# Sheet1.net
KiCad netlist of a schematic drawn in Altium Designer
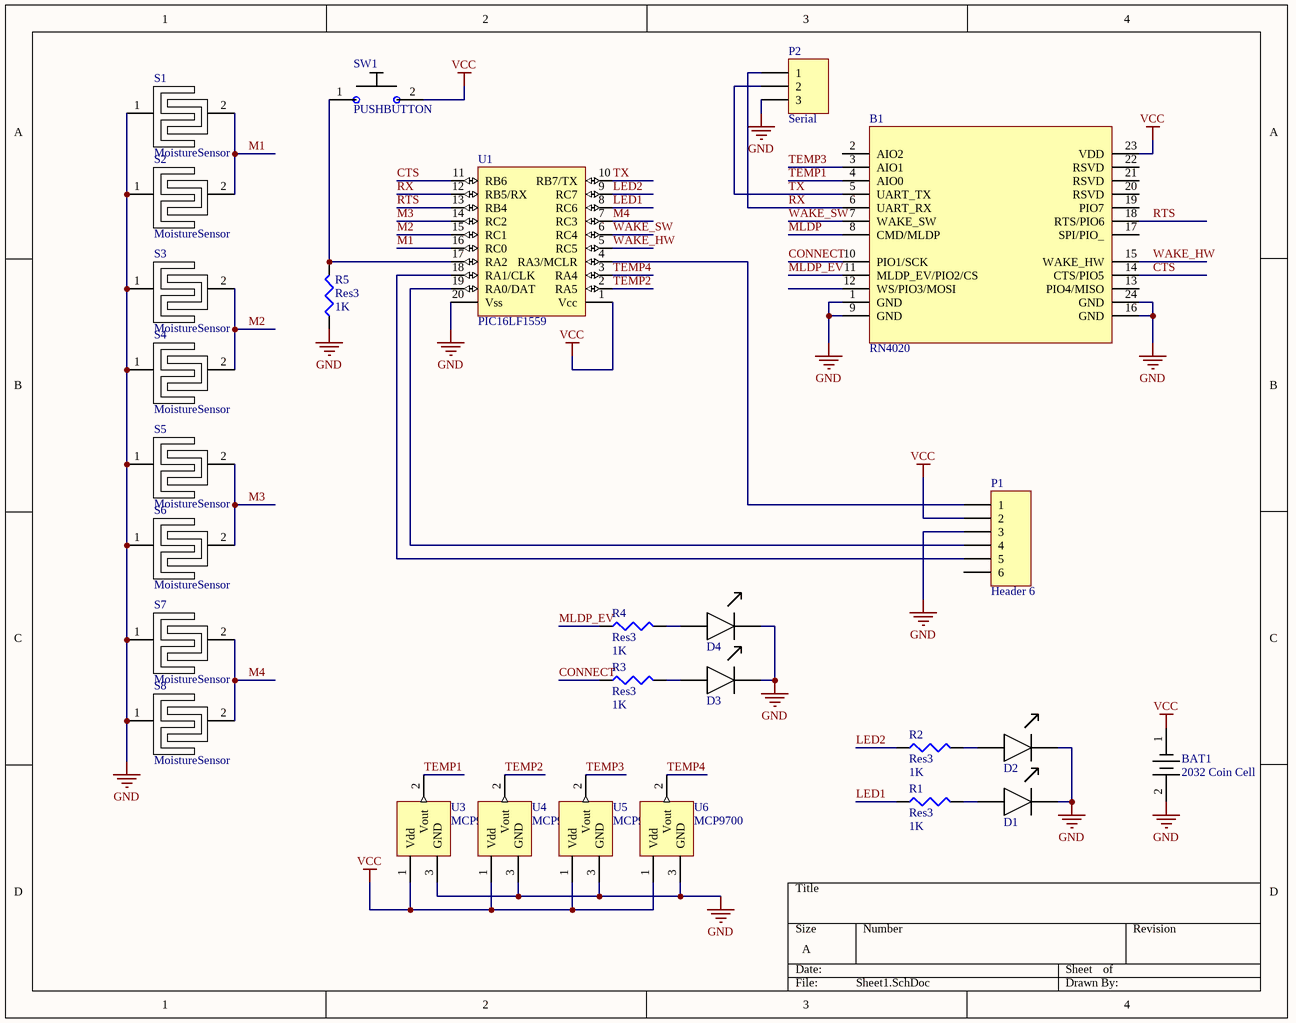
[diagram p0: Sheet1.SchDoc]

(export (version "E")
  (design (tool "Eeschema 10.0.6"))
  (components
    (comp (ref "B1") (value "RN4020") (footprint "RN4020 MODULE-24") (libsource (lib "Phil") (part "RN4020")))
    (comp (ref "BAT1")
      (value "2032 Coin Cell")
      (footprint "1063TR-CoinCell")
      (libsource (lib "Phil") (part "2032 Coin Cell"))
    )
    (comp (ref "D1") (value "LED") (footprint "603_") (libsource (lib "Phil") (part "LED")))
    (comp (ref "D2") (value "LED") (footprint "603_") (libsource (lib "Phil") (part "LED")))
    (comp (ref "D3") (value "LED") (footprint "603_") (libsource (lib "Phil") (part "LED")))
    (comp (ref "D4") (value "LED") (footprint "603_") (libsource (lib "Phil") (part "LED")))
    (comp (ref "P1")
      (value "Header 6")
      (footprint "HDR1X6")
      (description "Header, 6-Pin")
      (fields (field (name "PUBLISHER") "Altium Limited"))
      (libsource (lib "Miscellaneous Connectors") (part "Header 6"))
    )
    (comp (ref "P2")
      (value "Serial")
      (footprint "HDR1X3")
      (description "Header, 3-Pin")
      (fields (field (name "PUBLISHER") "Altium Limited"))
      (libsource (lib "Miscellaneous Connectors") (part "Header 3"))
    )
    (comp (ref "R1")
      (value "Res3")
      (footprint "J1-0603")
      (description "Resistor")
      (fields (field (name "ALTIUM_VALUE") "1K") (field (name "PUBLISHER") "Altium Limited"))
      (libsource (lib "Miscellaneous Devices") (part "Res3"))
    )
    (comp (ref "R2")
      (value "Res3")
      (footprint "J1-0603")
      (description "Resistor")
      (fields (field (name "ALTIUM_VALUE") "1K") (field (name "PUBLISHER") "Altium Limited"))
      (libsource (lib "Miscellaneous Devices") (part "Res3"))
    )
    (comp (ref "R3")
      (value "Res3")
      (footprint "J1-0603")
      (description "Resistor")
      (fields (field (name "ALTIUM_VALUE") "1K") (field (name "PUBLISHER") "Altium Limited"))
      (libsource (lib "Miscellaneous Devices") (part "Res3"))
    )
    (comp (ref "R4")
      (value "Res3")
      (footprint "J1-0603")
      (description "Resistor")
      (fields (field (name "ALTIUM_VALUE") "1K") (field (name "PUBLISHER") "Altium Limited"))
      (libsource (lib "Miscellaneous Devices") (part "Res3"))
    )
    (comp (ref "R5")
      (value "Res3")
      (footprint "J1-0603")
      (description "Resistor")
      (fields (field (name "ALTIUM_VALUE") "1K") (field (name "PUBLISHER") "Altium Limited"))
      (libsource (lib "Miscellaneous Devices") (part "Res3"))
    )
    (comp (ref "S1")
      (value "MoistureSensor")
      (footprint "MOISTURE_2")
      (libsource (lib "Phil") (part "MoistureSensor"))
    )
    (comp (ref "S2")
      (value "MoistureSensor")
      (footprint "MOISTURE_2")
      (libsource (lib "Phil") (part "MoistureSensor"))
    )
    (comp (ref "S3")
      (value "MoistureSensor")
      (footprint "MOISTURE_2")
      (libsource (lib "Phil") (part "MoistureSensor"))
    )
    (comp (ref "S4")
      (value "MoistureSensor")
      (footprint "MOISTURE_2")
      (libsource (lib "Phil") (part "MoistureSensor"))
    )
    (comp (ref "S5")
      (value "MoistureSensor")
      (footprint "MOISTURE_2")
      (libsource (lib "Phil") (part "MoistureSensor"))
    )
    (comp (ref "S6")
      (value "MoistureSensor")
      (footprint "MOISTURE_2")
      (libsource (lib "Phil") (part "MoistureSensor"))
    )
    (comp (ref "S7")
      (value "MoistureSensor")
      (footprint "MOISTURE_2")
      (libsource (lib "Phil") (part "MoistureSensor"))
    )
    (comp (ref "S8")
      (value "MoistureSensor")
      (footprint "MOISTURE_2")
      (libsource (lib "Phil") (part "MoistureSensor"))
    )
    (comp (ref "SW1")
      (value "PUSHBUTTON")
      (footprint "PUSHBUTTON")
      (description "TE 5-1437565-0")
      (libsource (lib "Phil") (part "PUSHBUTTON"))
    )
    (comp (ref "U1")
      (value "PIC16LF1559")
      (footprint "SSOP-20")
      (libsource (lib "Phil") (part "PIC16LF1559"))
    )
    (comp (ref "U3")
      (value "MCP9700")
      (footprint "Miscellaneous Devices:SOT23_M")
      (libsource (lib "Phil") (part "MCP9700"))
    )
    (comp (ref "U4")
      (value "MCP9700")
      (footprint "Miscellaneous Devices:SOT23_M")
      (libsource (lib "Phil") (part "MCP9700"))
    )
    (comp (ref "U5")
      (value "MCP9700")
      (footprint "Miscellaneous Devices:SOT23_M")
      (libsource (lib "Phil") (part "MCP9700"))
    )
    (comp (ref "U6")
      (value "MCP9700")
      (footprint "Miscellaneous Devices:SOT23_M")
      (libsource (lib "Phil") (part "MCP9700"))
    )
  )
  (nets
    (net (code "1") (name "/CONNECT") (class "Default")
      (node (ref "B1") (pin "10") (pinfunction "PIO1/SCK_10") (pintype "passive"))
      (node (ref "R3") (pin "1") (pinfunction "1_1") (pintype "passive"))
    )
    (net (code "2") (name "/CTS") (class "Default")
      (node (ref "B1") (pin "14") (pinfunction "CTS/PIO5_14") (pintype "passive"))
      (node (ref "U1") (pin "11") (pinfunction "RB6_11") (pintype "bidirectional"))
    )
    (net (code "3") (name "/LED1") (class "Default")
      (node (ref "R1") (pin "1") (pinfunction "1_1") (pintype "passive"))
      (node (ref "U1") (pin "8") (pinfunction "RC6_8") (pintype "bidirectional"))
    )
    (net (code "4") (name "/LED2") (class "Default")
      (node (ref "R2") (pin "1") (pinfunction "1_1") (pintype "passive"))
      (node (ref "U1") (pin "9") (pinfunction "RC7_9") (pintype "bidirectional"))
    )
    (net (code "5") (name "/M1") (class "Default")
      (node (ref "S1") (pin "2") (pinfunction "2_2") (pintype "passive"))
      (node (ref "S2") (pin "2") (pinfunction "2_2") (pintype "passive"))
      (node (ref "U1") (pin "16") (pinfunction "RC0_16") (pintype "bidirectional"))
    )
    (net (code "6") (name "/M2") (class "Default")
      (node (ref "S3") (pin "2") (pinfunction "2_2") (pintype "passive"))
      (node (ref "S4") (pin "2") (pinfunction "2_2") (pintype "passive"))
      (node (ref "U1") (pin "15") (pinfunction "RC1_15") (pintype "bidirectional"))
    )
    (net (code "7") (name "/M3") (class "Default")
      (node (ref "S5") (pin "2") (pinfunction "2_2") (pintype "passive"))
      (node (ref "S6") (pin "2") (pinfunction "2_2") (pintype "passive"))
      (node (ref "U1") (pin "14") (pinfunction "RC2_14") (pintype "bidirectional"))
    )
    (net (code "8") (name "/M4") (class "Default")
      (node (ref "S7") (pin "2") (pinfunction "2_2") (pintype "passive"))
      (node (ref "S8") (pin "2") (pinfunction "2_2") (pintype "passive"))
      (node (ref "U1") (pin "7") (pinfunction "RC3_7") (pintype "bidirectional"))
    )
    (net (code "9") (name "/MLDP") (class "Default")
      (node (ref "B1") (pin "8") (pinfunction "CMD/MLDP_8") (pintype "passive"))
    )
    (net (code "10") (name "/MLDP_EV") (class "Default")
      (node (ref "B1") (pin "11") (pinfunction "MLDP_EV/PIO2/CS_11") (pintype "passive"))
      (node (ref "R4") (pin "1") (pinfunction "1_1") (pintype "passive"))
    )
    (net (code "11") (name "/RTS") (class "Default")
      (node (ref "B1") (pin "18") (pinfunction "RTS/PIO6_18") (pintype "passive"))
      (node (ref "U1") (pin "13") (pinfunction "RB4_13") (pintype "bidirectional"))
    )
    (net (code "12") (name "/RX") (class "Default")
      (node (ref "B1") (pin "6") (pinfunction "UART_RX_6") (pintype "passive"))
      (node (ref "P2") (pin "1") (pinfunction "1_1") (pintype "passive"))
      (node (ref "U1") (pin "12") (pinfunction "RB5/RX_12") (pintype "bidirectional"))
    )
    (net (code "13") (name "/TEMP1") (class "Default")
      (node (ref "B1") (pin "4") (pinfunction "AIO0_4") (pintype "passive"))
      (node (ref "U3") (pin "2") (pinfunction "Vout_2") (pintype "output"))
    )
    (net (code "14") (name "/TEMP2") (class "Default")
      (node (ref "U1") (pin "2") (pinfunction "RA5_2") (pintype "bidirectional"))
      (node (ref "U4") (pin "2") (pinfunction "Vout_2") (pintype "output"))
    )
    (net (code "15") (name "/TEMP3") (class "Default")
      (node (ref "B1") (pin "3") (pinfunction "AIO1_3") (pintype "passive"))
      (node (ref "U5") (pin "2") (pinfunction "Vout_2") (pintype "output"))
    )
    (net (code "16") (name "/TEMP4") (class "Default")
      (node (ref "U1") (pin "3") (pinfunction "RA4_3") (pintype "bidirectional"))
      (node (ref "U6") (pin "2") (pinfunction "Vout_2") (pintype "output"))
    )
    (net (code "17") (name "/TX") (class "Default")
      (node (ref "B1") (pin "5") (pinfunction "UART_TX_5") (pintype "passive"))
      (node (ref "P2") (pin "2") (pinfunction "2_2") (pintype "passive"))
      (node (ref "U1") (pin "10") (pinfunction "RB7/TX_10") (pintype "bidirectional"))
    )
    (net (code "18") (name "/WAKE_HW") (class "Default")
      (node (ref "B1") (pin "15") (pinfunction "WAKE_HW_15") (pintype "passive"))
      (node (ref "U1") (pin "5") (pinfunction "RC5_5") (pintype "bidirectional"))
    )
    (net (code "19") (name "/WAKE_SW") (class "Default")
      (node (ref "B1") (pin "7") (pinfunction "WAKE_SW_7") (pintype "passive"))
      (node (ref "U1") (pin "6") (pinfunction "RC4_6") (pintype "bidirectional"))
    )
    (net (code "20") (name "GND") (class "Default")
      (node (ref "B1") (pin "1") (pinfunction "GND_1") (pintype "power_in"))
      (node (ref "B1") (pin "16") (pinfunction "GND_16") (pintype "power_in"))
      (node (ref "B1") (pin "24") (pinfunction "GND_24") (pintype "passive"))
      (node (ref "B1") (pin "9") (pinfunction "GND_9") (pintype "power_in"))
      (node (ref "BAT1") (pin "2") (pinfunction "2_2") (pintype "passive"))
      (node (ref "D1") (pin "2") (pinfunction "2_2") (pintype "passive"))
      (node (ref "D2") (pin "2") (pinfunction "2_2") (pintype "passive"))
      (node (ref "D3") (pin "2") (pinfunction "2_2") (pintype "passive"))
      (node (ref "D4") (pin "2") (pinfunction "2_2") (pintype "passive"))
      (node (ref "P1") (pin "3") (pinfunction "3_3") (pintype "passive"))
      (node (ref "P2") (pin "3") (pinfunction "3_3") (pintype "passive"))
      (node (ref "R5") (pin "1") (pinfunction "1_1") (pintype "passive"))
      (node (ref "S1") (pin "1") (pinfunction "1_1") (pintype "passive"))
      (node (ref "S2") (pin "1") (pinfunction "1_1") (pintype "passive"))
      (node (ref "S3") (pin "1") (pinfunction "1_1") (pintype "passive"))
      (node (ref "S4") (pin "1") (pinfunction "1_1") (pintype "passive"))
      (node (ref "S5") (pin "1") (pinfunction "1_1") (pintype "passive"))
      (node (ref "S6") (pin "1") (pinfunction "1_1") (pintype "passive"))
      (node (ref "S7") (pin "1") (pinfunction "1_1") (pintype "passive"))
      (node (ref "S8") (pin "1") (pinfunction "1_1") (pintype "passive"))
      (node (ref "U1") (pin "20") (pinfunction "Vss_20") (pintype "power_in"))
      (node (ref "U3") (pin "3") (pinfunction "GND_3") (pintype "power_in"))
      (node (ref "U4") (pin "3") (pinfunction "GND_3") (pintype "power_in"))
      (node (ref "U5") (pin "3") (pinfunction "GND_3") (pintype "power_in"))
      (node (ref "U6") (pin "3") (pinfunction "GND_3") (pintype "power_in"))
    )
    (net (code "21") (name "Net-(D1-Pad1)") (class "Default")
      (node (ref "D1") (pin "1") (pinfunction "1_1") (pintype "passive"))
      (node (ref "R1") (pin "2") (pinfunction "2_2") (pintype "passive"))
    )
    (net (code "22") (name "Net-(D2-Pad1)") (class "Default")
      (node (ref "D2") (pin "1") (pinfunction "1_1") (pintype "passive"))
      (node (ref "R2") (pin "2") (pinfunction "2_2") (pintype "passive"))
    )
    (net (code "23") (name "Net-(D3-Pad1)") (class "Default")
      (node (ref "D3") (pin "1") (pinfunction "1_1") (pintype "passive"))
      (node (ref "R3") (pin "2") (pinfunction "2_2") (pintype "passive"))
    )
    (net (code "24") (name "Net-(D4-Pad1)") (class "Default")
      (node (ref "D4") (pin "1") (pinfunction "1_1") (pintype "passive"))
      (node (ref "R4") (pin "2") (pinfunction "2_2") (pintype "passive"))
    )
    (net (code "25") (name "Net-(U1-RA0{slash}DAT)") (class "Default")
      (node (ref "P1") (pin "4") (pinfunction "4_4") (pintype "passive"))
      (node (ref "U1") (pin "19") (pinfunction "RA0/DAT_19") (pintype "bidirectional"))
    )
    (net (code "26") (name "Net-(U1-RA1{slash}CLK)") (class "Default")
      (node (ref "P1") (pin "5") (pinfunction "5_5") (pintype "passive"))
      (node (ref "U1") (pin "18") (pinfunction "RA1/CLK_18") (pintype "bidirectional"))
    )
    (net (code "27") (name "Net-(U1-RA2)") (class "Default")
      (node (ref "R5") (pin "2") (pinfunction "2_2") (pintype "passive"))
      (node (ref "SW1") (pin "1") (pinfunction "1_1") (pintype "passive"))
      (node (ref "U1") (pin "17") (pinfunction "RA2_17") (pintype "bidirectional"))
    )
    (net (code "28") (name "Net-(U1-RA3{slash}MCLR)") (class "Default")
      (node (ref "P1") (pin "1") (pinfunction "1_1") (pintype "passive"))
      (node (ref "U1") (pin "4") (pinfunction "RA3/MCLR_4") (pintype "bidirectional"))
    )
    (net (code "29") (name "VCC") (class "Default")
      (node (ref "B1") (pin "23") (pinfunction "VDD_23") (pintype "power_in"))
      (node (ref "BAT1") (pin "1") (pinfunction "1_1") (pintype "passive"))
      (node (ref "P1") (pin "2") (pinfunction "2_2") (pintype "passive"))
      (node (ref "SW1") (pin "2") (pinfunction "2_2") (pintype "passive"))
      (node (ref "U1") (pin "1") (pinfunction "Vcc_1") (pintype "power_in"))
      (node (ref "U3") (pin "1") (pinfunction "Vdd_1") (pintype "power_in"))
      (node (ref "U4") (pin "1") (pinfunction "Vdd_1") (pintype "power_in"))
      (node (ref "U5") (pin "1") (pinfunction "Vdd_1") (pintype "power_in"))
      (node (ref "U6") (pin "1") (pinfunction "Vdd_1") (pintype "power_in"))
    )
    (net (code "30") (name "unconnected-(B1-AIO2-Pad2)") (class "Default")
      (node (ref "B1") (pin "2") (pinfunction "AIO2_2") (pintype "passive"))
    )
    (net (code "31") (name "unconnected-(B1-PIO4{slash}MISO-Pad13)") (class "Default")
      (node (ref "B1") (pin "13") (pinfunction "PIO4/MISO_13") (pintype "passive"))
    )
    (net (code "32") (name "unconnected-(B1-PIO7-Pad19)") (class "Default")
      (node (ref "B1") (pin "19") (pinfunction "PIO7_19") (pintype "passive"))
    )
    (net (code "33") (name "unconnected-(B1-RSVD-Pad20)") (class "Default")
      (node (ref "B1") (pin "20") (pinfunction "RSVD_20") (pintype "passive"))
    )
    (net (code "34") (name "unconnected-(B1-RSVD-Pad21)") (class "Default")
      (node (ref "B1") (pin "21") (pinfunction "RSVD_21") (pintype "passive"))
    )
    (net (code "35") (name "unconnected-(B1-RSVD-Pad22)") (class "Default")
      (node (ref "B1") (pin "22") (pinfunction "RSVD_22") (pintype "passive"))
    )
    (net (code "36") (name "unconnected-(B1-SPI{slash}PIO_-Pad17)") (class "Default")
      (node (ref "B1") (pin "17") (pinfunction "SPI/PIO__17") (pintype "passive"))
    )
    (net (code "37") (name "unconnected-(B1-WS{slash}PIO3{slash}MOSI-Pad12)") (class "Default")
      (node (ref "B1") (pin "12") (pinfunction "WS/PIO3/MOSI_12") (pintype "passive"))
    )
    (net (code "38") (name "unconnected-(P1-Pad6)") (class "Default")
      (node (ref "P1") (pin "6") (pinfunction "6_6") (pintype "passive"))
    )
  )
)
